# SPI_To_Ethernet.net
KiCad netlist of a schematic drawn in Altium Designer
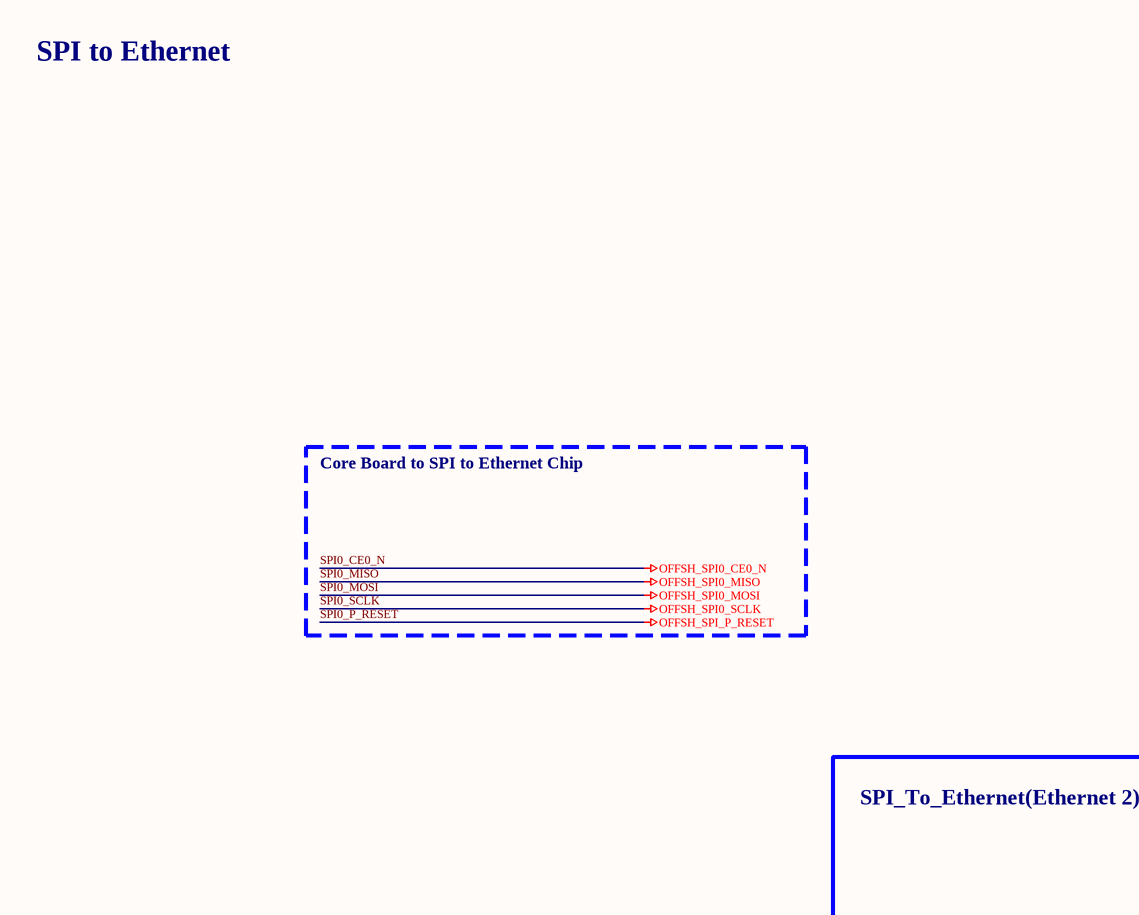
[diagram p0: SPI_To_Ethernet.SchDoc, top left]
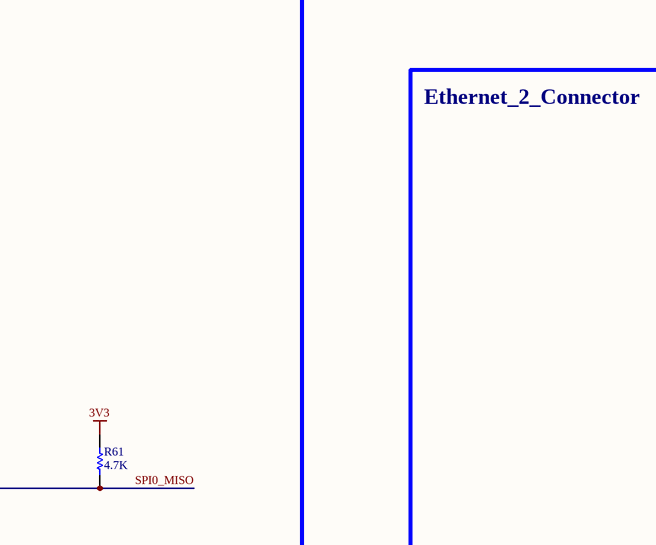
[diagram p1: SPI_To_Ethernet.SchDoc, top right]
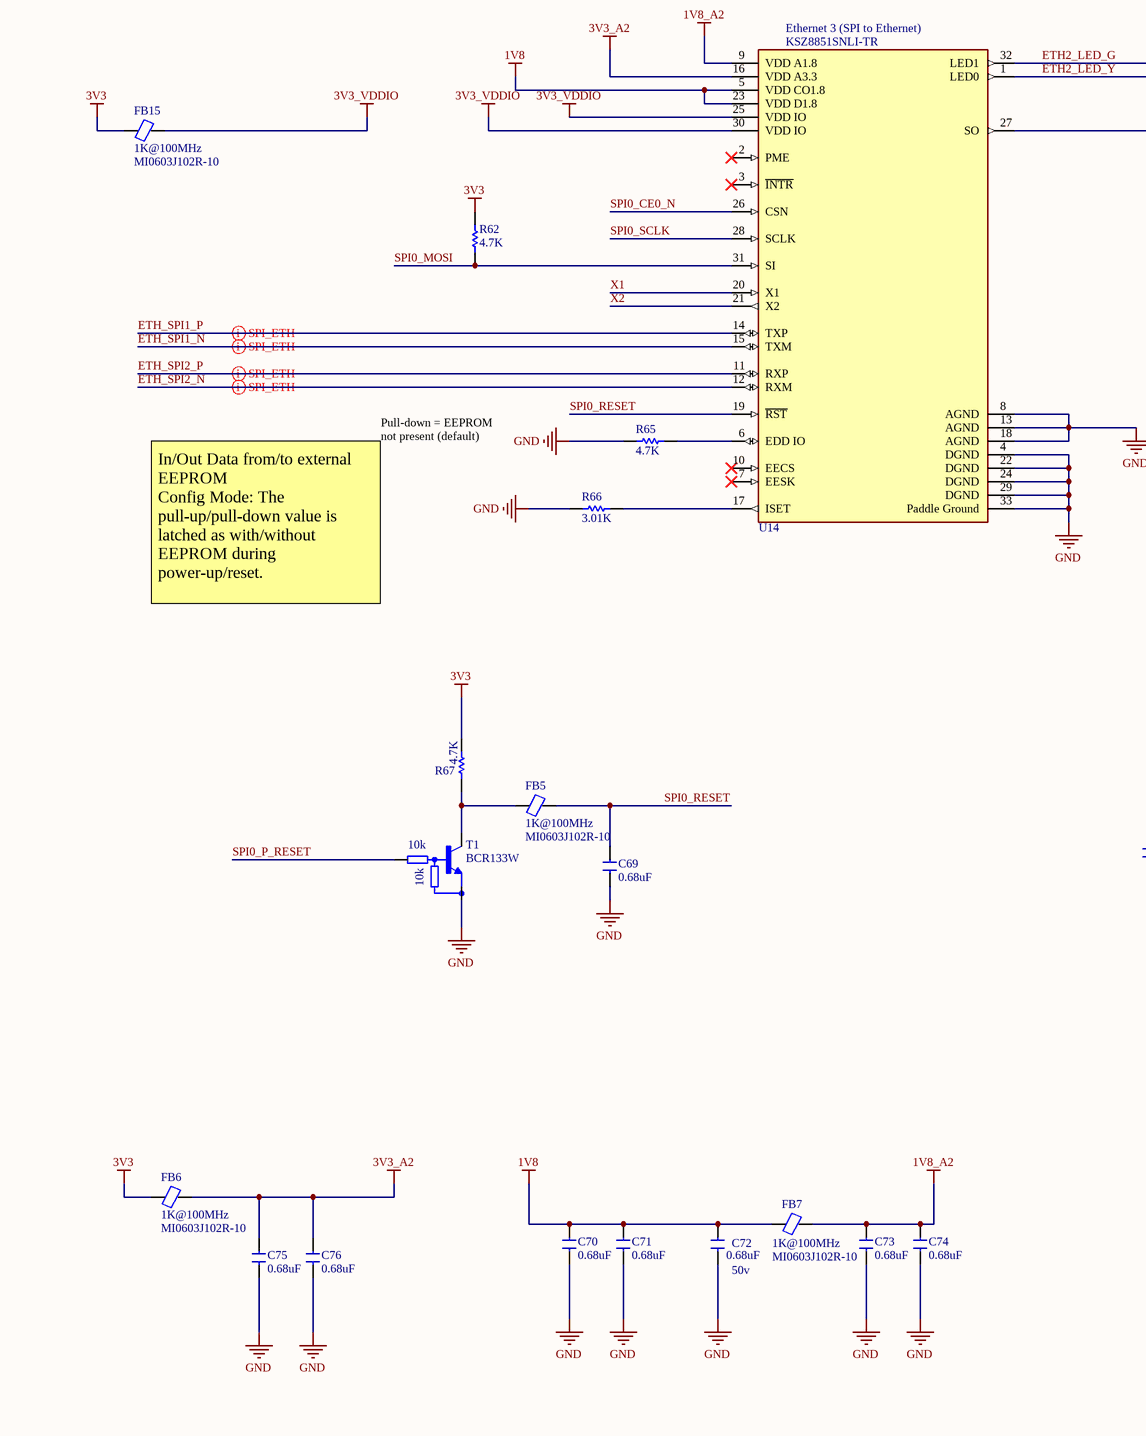
[diagram p2: SPI_To_Ethernet.SchDoc, bottom left]
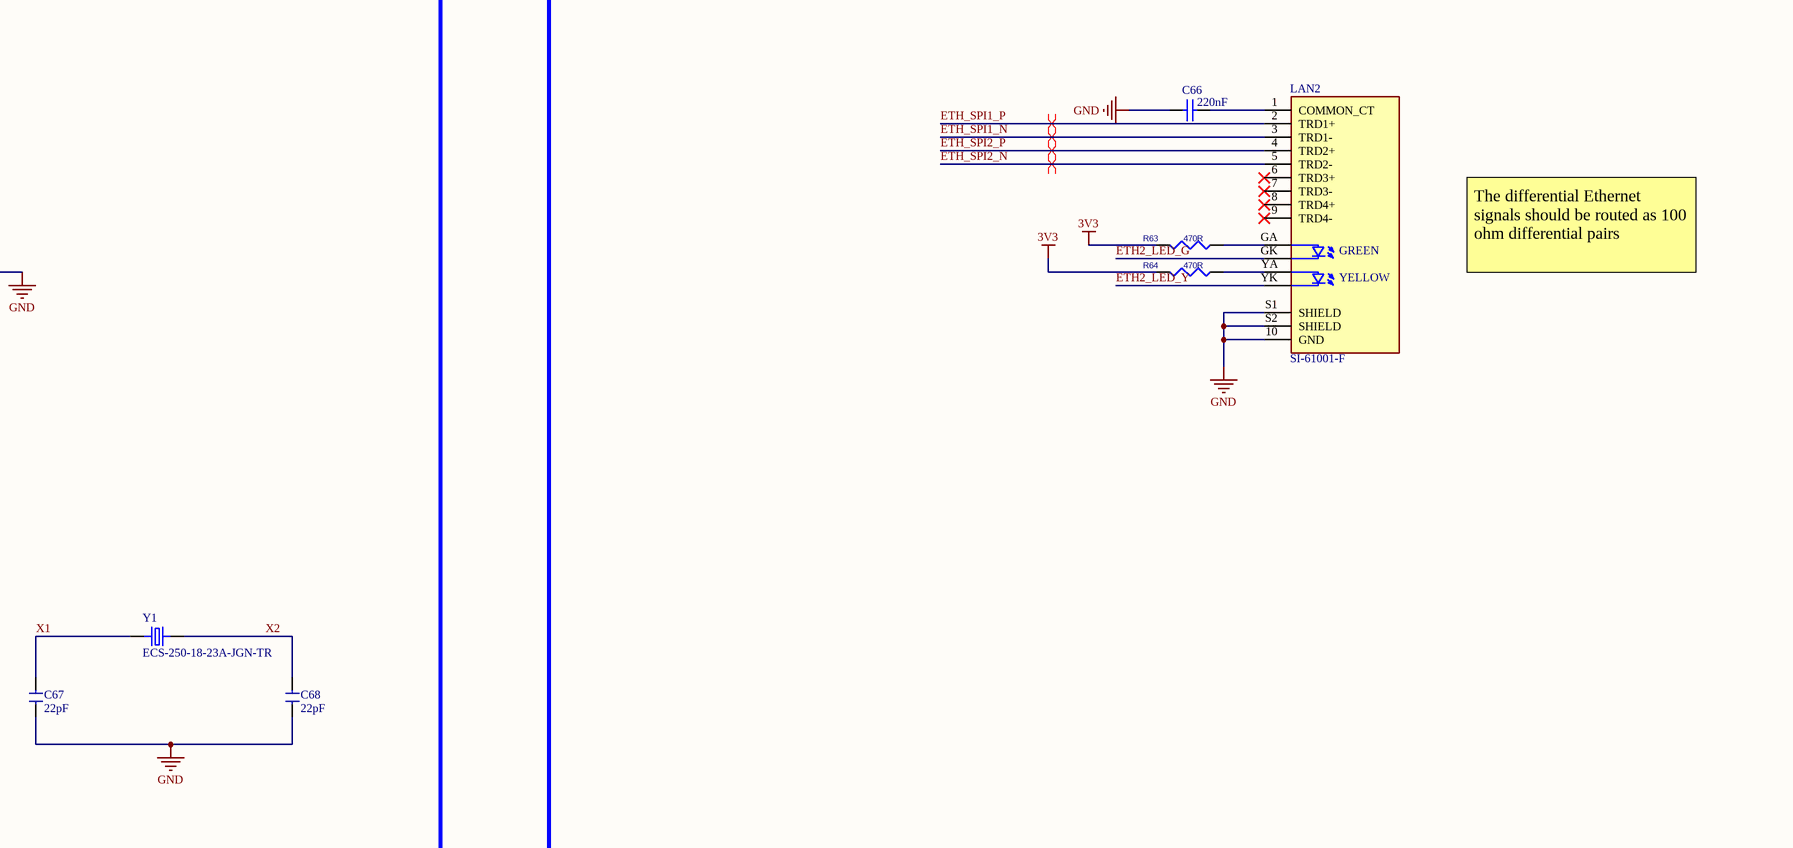
[diagram p3: SPI_To_Ethernet.SchDoc, bottom right]

(export (version "E")
  (design (tool "Eeschema 10.0.6"))
  (components
    (comp (ref "C66")
      (value "220nF")
      (footprint "CAP (0603)")
      (description "SMD capacitor")
      (fields (field (name "PART NUMBER") "SMD CAP (0603)") (field (name "Comment") "Cap"))
      (libsource (lib "CC") (part "Cap"))
    )
    (comp (ref "C67")
      (value "22pF")
      (footprint "0603 Capacitor")
      (fields (field (name "VOLTAGE") "50v") (field (name "Comment") "Capacitor SMD"))
      (libsource (lib "SA-C7_Apr09") (part "Capacitor SMD"))
    )
    (comp (ref "C68")
      (value "22pF")
      (footprint "0603 Capacitor")
      (fields (field (name "VOLTAGE") "50v") (field (name "Comment") "Capacitor SMD"))
      (libsource (lib "SA-C7_Apr09") (part "Capacitor SMD"))
    )
    (comp (ref "C69")
      (value "0.68uF")
      (footprint "0603 Capacitor")
      (fields (field (name "VOLTAGE") "50v") (field (name "Comment") "Capacitor SMD"))
      (libsource (lib "SA-C7_Apr09") (part "Capacitor SMD"))
    )
    (comp (ref "C70")
      (value "0.68uF")
      (footprint "0603 Capacitor")
      (fields (field (name "VOLTAGE") "50v") (field (name "Comment") "Capacitor SMD"))
      (libsource (lib "SA-C7_Apr09") (part "Capacitor SMD"))
    )
    (comp (ref "C71")
      (value "0.68uF")
      (footprint "0603 Capacitor")
      (fields (field (name "VOLTAGE") "50v") (field (name "Comment") "Capacitor SMD"))
      (libsource (lib "SA-C7_Apr09") (part "Capacitor SMD"))
    )
    (comp (ref "C72")
      (value "0.68uF")
      (footprint "0603 Capacitor")
      (fields (field (name "VOLTAGE") "50v") (field (name "Comment") "Capacitor SMD"))
      (libsource (lib "SA-C7_Apr09") (part "Capacitor SMD"))
    )
    (comp (ref "C73")
      (value "0.68uF")
      (footprint "0603 Capacitor")
      (fields (field (name "VOLTAGE") "50v") (field (name "Comment") "Capacitor SMD"))
      (libsource (lib "SA-C7_Apr09") (part "Capacitor SMD"))
    )
    (comp (ref "C74")
      (value "0.68uF")
      (footprint "0603 Capacitor")
      (fields (field (name "VOLTAGE") "50v") (field (name "Comment") "Capacitor SMD"))
      (libsource (lib "SA-C7_Apr09") (part "Capacitor SMD"))
    )
    (comp (ref "C75")
      (value "0.68uF")
      (footprint "0603 Capacitor")
      (fields (field (name "VOLTAGE") "50v") (field (name "Comment") "Capacitor SMD"))
      (libsource (lib "SA-C7_Apr09") (part "Capacitor SMD"))
    )
    (comp (ref "C76")
      (value "0.68uF")
      (footprint "0603 Capacitor")
      (fields (field (name "VOLTAGE") "50v") (field (name "Comment") "Capacitor SMD"))
      (libsource (lib "SA-C7_Apr09") (part "Capacitor SMD"))
    )
    (comp (ref "FB5")
      (value "1K@100MHz")
      (footprint "FB0603")
      (description "Ferrite Bead SMD")
      (fields (field (name "PART NUMBER") "MI0603J102R-10") (field (name "Comment") "Ferrite Bead"))
      (libsource (lib "*") (part "Ferrite Bead"))
    )
    (comp (ref "FB6")
      (value "1K@100MHz")
      (footprint "FB0603")
      (description "Ferrite Bead SMD")
      (fields (field (name "PART NUMBER") "MI0603J102R-10") (field (name "Comment") "Ferrite Bead"))
      (libsource (lib "*") (part "Ferrite Bead"))
    )
    (comp (ref "FB7")
      (value "1K@100MHz")
      (footprint "FB0603")
      (description "Ferrite Bead SMD")
      (fields (field (name "PART NUMBER") "MI0603J102R-10") (field (name "Comment") "Ferrite Bead"))
      (libsource (lib "*") (part "Ferrite Bead"))
    )
    (comp (ref "FB15")
      (value "1K@100MHz")
      (footprint "FB0603")
      (description "Ferrite Bead SMD")
      (fields (field (name "PART NUMBER") "MI0603J102R-10") (field (name "Comment") "Ferrite Bead"))
      (libsource (lib "*") (part "Ferrite Bead"))
    )
    (comp (ref "LAN2")
      (value "SI-61001-F")
      (footprint "SI-61001-F_with3D:BEL_SI-61001-F")
      (description "Conn RJ-45 RCP 8 POS 1.27mm Solder RA Thru-Hole 14 Terminal 1 Port")
      (fields (field (name "MF") "Bel Magnetic Solutions"))
      (libsource (lib "SI-61001-F (1)") (part "SI-61001-F"))
    )
    (comp (ref "R61")
      (value "4.7K")
      (footprint "R0603")
      (description "Resistor")
      (fields (field (name "Comment") "Res") (field (name "PUBLISHER") "Altium Limited"))
      (libsource (lib "SCV500+") (part "Res"))
    )
    (comp (ref "R62")
      (value "4.7K")
      (footprint "R0603")
      (description "Resistor")
      (fields (field (name "Comment") "Res") (field (name "PUBLISHER") "Altium Limited"))
      (libsource (lib "SCV500+") (part "Res"))
    )
    (comp (ref "R63") (value "470R") (footprint "R0603") (libsource (lib "*") (part "RES")))
    (comp (ref "R64") (value "470R") (footprint "R0603") (libsource (lib "*") (part "RES")))
    (comp (ref "R65")
      (value "4.7K")
      (footprint "R0603")
      (description "Resistor")
      (fields (field (name "Comment") "Res") (field (name "PUBLISHER") "Altium Limited"))
      (libsource (lib "SCV500+") (part "Res"))
    )
    (comp (ref "R66")
      (value "3.01K")
      (footprint "R0603")
      (description "Resistor")
      (fields (field (name "Comment") "Res") (field (name "PUBLISHER") "Altium Limited"))
      (libsource (lib "SCV500+") (part "Res"))
    )
    (comp (ref "R67")
      (value "4.7K")
      (footprint "R0603")
      (description "Resistor")
      (fields (field (name "Comment") "Res") (field (name "PUBLISHER") "Altium Limited"))
      (libsource (lib "SCV500+") (part "Res"))
    )
    (comp (ref "T1")
      (value "BCR133W")
      (footprint "SOT323-BEC")
      (description "<b>NPN Silicon Digital Transistor</b>  50V 0,1A 0,25W")
      (libsource (lib "BCR133W") (part "BCR133W"))
    )
    (comp (ref "U14")
      (value "KSZ8851SNLI-TR")
      (footprint "QFN50P500X500X90-33N")
      (libsource (lib "IC_Microchip_KSZ8851SNLI-TR_eec") (part "KSZ8851SNLI-TR"))
    )
    (comp (ref "Y1")
      (value "ECS-250-18-23A-JGN-TR")
      (footprint "XTAL_ECS-250-18-23A-JGN-TR")
      (description "Crystal 2-SMD, No Lead")
      (libsource (lib "ECS-250-18-23A-JGN-TR") (part "ECS-250-18-23A-JGN-TR"))
    )
  )
  (nets
    (net (code "1") (name "/ETH2_LED_G") (class "Default")
      (node (ref "LAN2") (pin "GK") (pinfunction "GK_GK") (pintype "passive"))
      (node (ref "U14") (pin "32") (pinfunction "LED1_32") (pintype "output"))
    )
    (net (code "2") (name "/ETH2_LED_Y") (class "Default")
      (node (ref "LAN2") (pin "YK") (pinfunction "YK_YK") (pintype "passive"))
      (node (ref "U14") (pin "1") (pinfunction "LED0_1") (pintype "output"))
    )
    (net (code "3") (name "/ETH_SPI1_N") (class "Default")
      (node (ref "LAN2") (pin "3") (pinfunction "TRD1-_3") (pintype "passive"))
      (node (ref "U14") (pin "15") (pinfunction "TXM_15") (pintype "bidirectional"))
    )
    (net (code "4") (name "/ETH_SPI1_P") (class "Default")
      (node (ref "LAN2") (pin "2") (pinfunction "TRD1+_2") (pintype "passive"))
      (node (ref "U14") (pin "14") (pinfunction "TXP_14") (pintype "bidirectional"))
    )
    (net (code "5") (name "/ETH_SPI2_N") (class "Default")
      (node (ref "LAN2") (pin "5") (pinfunction "TRD2-_5") (pintype "passive"))
      (node (ref "U14") (pin "12") (pinfunction "RXM_12") (pintype "bidirectional"))
    )
    (net (code "6") (name "/ETH_SPI2_P") (class "Default")
      (node (ref "LAN2") (pin "4") (pinfunction "TRD2+_4") (pintype "passive"))
      (node (ref "U14") (pin "11") (pinfunction "RXP_11") (pintype "bidirectional"))
    )
    (net (code "7") (name "/SPI0_RESET") (class "Default")
      (node (ref "C69") (pin "1") (pintype "passive"))
      (node (ref "FB5") (pin "2") (pinfunction "2_2") (pintype "passive"))
      (node (ref "U14") (pin "19") (pinfunction "~{RST}_19") (pintype "input"))
    )
    (net (code "8") (name "/X1") (class "Default")
      (node (ref "C67") (pin "1") (pintype "passive"))
      (node (ref "U14") (pin "20") (pinfunction "X1_20") (pintype "input"))
      (node (ref "Y1") (pin "1") (pinfunction "IN/OUT_1") (pintype "passive"))
    )
    (net (code "9") (name "/X2") (class "Default")
      (node (ref "C68") (pin "1") (pintype "passive"))
      (node (ref "U14") (pin "21") (pinfunction "X2_21") (pintype "output"))
      (node (ref "Y1") (pin "2") (pinfunction "OUT/IN_2") (pintype "passive"))
    )
    (net (code "10") (name "1V8") (class "Default")
      (node (ref "C70") (pin "1") (pintype "passive"))
      (node (ref "C71") (pin "1") (pintype "passive"))
      (node (ref "C72") (pin "2") (pintype "passive"))
      (node (ref "FB7") (pin "1") (pinfunction "1_1") (pintype "passive"))
      (node (ref "U14") (pin "23") (pinfunction "VDD_D1.8_23") (pintype "power_in"))
      (node (ref "U14") (pin "5") (pinfunction "VDD_CO1.8_5") (pintype "power_in"))
    )
    (net (code "11") (name "1V8_A2") (class "Default")
      (node (ref "C73") (pin "1") (pintype "passive"))
      (node (ref "C74") (pin "1") (pintype "passive"))
      (node (ref "FB7") (pin "2") (pinfunction "2_2") (pintype "passive"))
      (node (ref "U14") (pin "9") (pinfunction "VDD_A1.8_9") (pintype "power_in"))
    )
    (net (code "12") (name "3V3") (class "Default")
      (node (ref "FB15") (pin "1") (pinfunction "1_1") (pintype "passive"))
      (node (ref "FB6") (pin "1") (pinfunction "1_1") (pintype "passive"))
      (node (ref "R61") (pin "2") (pinfunction "2_2") (pintype "passive"))
      (node (ref "R62") (pin "2") (pinfunction "2_2") (pintype "passive"))
      (node (ref "R63") (pin "1") (pinfunction "1_1") (pintype "passive"))
      (node (ref "R64") (pin "1") (pinfunction "1_1") (pintype "passive"))
      (node (ref "R67") (pin "2") (pinfunction "2_2") (pintype "passive"))
    )
    (net (code "13") (name "3V3_A2") (class "Default")
      (node (ref "C75") (pin "1") (pintype "passive"))
      (node (ref "C76") (pin "1") (pintype "passive"))
      (node (ref "FB6") (pin "2") (pinfunction "2_2") (pintype "passive"))
      (node (ref "U14") (pin "16") (pinfunction "VDD_A3.3_16") (pintype "power_in"))
    )
    (net (code "14") (name "3V3_VDDIO") (class "Default")
      (node (ref "FB15") (pin "2") (pinfunction "2_2") (pintype "passive"))
      (node (ref "U14") (pin "25") (pinfunction "VDD_IO_25") (pintype "power_in"))
      (node (ref "U14") (pin "30") (pinfunction "VDD_IO_30") (pintype "power_in"))
    )
    (net (code "15") (name "GND") (class "Default")
      (node (ref "C66") (pin "1") (pinfunction "1_1") (pintype "passive"))
      (node (ref "C67") (pin "2") (pintype "passive"))
      (node (ref "C68") (pin "2") (pintype "passive"))
      (node (ref "C69") (pin "2") (pintype "passive"))
      (node (ref "C70") (pin "2") (pintype "passive"))
      (node (ref "C71") (pin "2") (pintype "passive"))
      (node (ref "C72") (pin "1") (pintype "passive"))
      (node (ref "C73") (pin "2") (pintype "passive"))
      (node (ref "C74") (pin "2") (pintype "passive"))
      (node (ref "C75") (pin "2") (pintype "passive"))
      (node (ref "C76") (pin "2") (pintype "passive"))
      (node (ref "LAN2") (pin "10") (pinfunction "GND_10") (pintype "power_in"))
      (node (ref "LAN2") (pin "S1") (pinfunction "SHIELD_S1") (pintype "passive"))
      (node (ref "LAN2") (pin "S2") (pinfunction "SHIELD_S2") (pintype "passive"))
      (node (ref "R65") (pin "1") (pinfunction "1_1") (pintype "passive"))
      (node (ref "R66") (pin "1") (pinfunction "1_1") (pintype "passive"))
      (node (ref "T1") (pin "E") (pinfunction "E_E") (pintype "passive"))
      (node (ref "U14") (pin "13") (pinfunction "AGND_13") (pintype "power_in"))
      (node (ref "U14") (pin "18") (pinfunction "AGND_18") (pintype "power_in"))
      (node (ref "U14") (pin "22") (pinfunction "DGND_22") (pintype "power_in"))
      (node (ref "U14") (pin "24") (pinfunction "DGND_24") (pintype "power_in"))
      (node (ref "U14") (pin "29") (pinfunction "DGND_29") (pintype "power_in"))
      (node (ref "U14") (pin "33") (pinfunction "Paddle_Ground_33") (pintype "passive"))
      (node (ref "U14") (pin "4") (pinfunction "DGND_4") (pintype "power_in"))
      (node (ref "U14") (pin "8") (pinfunction "AGND_8") (pintype "power_in"))
    )
    (net (code "16") (name "Net-(FB5-Pad1)") (class "Default")
      (node (ref "FB5") (pin "1") (pinfunction "1_1") (pintype "passive"))
      (node (ref "R67") (pin "1") (pinfunction "1_1") (pintype "passive"))
      (node (ref "T1") (pin "C") (pinfunction "C_C") (pintype "passive"))
    )
    (net (code "17") (name "Net-(LAN2-COMMON_CT)") (class "Default")
      (node (ref "C66") (pin "2") (pinfunction "2_2") (pintype "passive"))
      (node (ref "LAN2") (pin "1") (pinfunction "COMMON_CT_1") (pintype "passive"))
    )
    (net (code "18") (name "Net-(LAN2-PadGA)") (class "Default")
      (node (ref "LAN2") (pin "GA") (pinfunction "GA_GA") (pintype "passive"))
      (node (ref "R63") (pin "2") (pinfunction "2_2") (pintype "passive"))
    )
    (net (code "19") (name "Net-(LAN2-PadYA)") (class "Default")
      (node (ref "LAN2") (pin "YA") (pinfunction "YA_YA") (pintype "passive"))
      (node (ref "R64") (pin "2") (pinfunction "2_2") (pintype "passive"))
    )
    (net (code "20") (name "Net-(U14-EDD_IO)") (class "Default")
      (node (ref "R65") (pin "2") (pinfunction "2_2") (pintype "passive"))
      (node (ref "U14") (pin "6") (pinfunction "EDD_IO_6") (pintype "bidirectional"))
    )
    (net (code "21") (name "Net-(U14-ISET)") (class "Default")
      (node (ref "R66") (pin "2") (pinfunction "2_2") (pintype "passive"))
      (node (ref "U14") (pin "17") (pinfunction "ISET_17") (pintype "output"))
    )
    (net (code "22") (name "OFFSH_SPI0_CE0_N") (class "Default")
      (node (ref "U14") (pin "26") (pinfunction "CSN_26") (pintype "input"))
    )
    (net (code "23") (name "OFFSH_SPI0_MISO") (class "Default")
      (node (ref "R61") (pin "1") (pinfunction "1_1") (pintype "passive"))
      (node (ref "U14") (pin "27") (pinfunction "SO_27") (pintype "output"))
    )
    (net (code "24") (name "OFFSH_SPI0_MOSI") (class "Default")
      (node (ref "R62") (pin "1") (pinfunction "1_1") (pintype "passive"))
      (node (ref "U14") (pin "31") (pinfunction "SI_31") (pintype "input"))
    )
    (net (code "25") (name "OFFSH_SPI0_SCLK") (class "Default")
      (node (ref "U14") (pin "28") (pinfunction "SCLK_28") (pintype "input"))
    )
    (net (code "26") (name "OFFSH_SPI_P_RESET") (class "Default")
      (node (ref "T1") (pin "B") (pinfunction "B_B") (pintype "passive"))
    )
    (net (code "27") (name "unconnected-(LAN2-TRD3+-Pad6)") (class "Default")
      (node (ref "LAN2") (pin "6") (pinfunction "TRD3+_6") (pintype "passive+no_connect"))
    )
    (net (code "28") (name "unconnected-(LAN2-TRD3--Pad7)") (class "Default")
      (node (ref "LAN2") (pin "7") (pinfunction "TRD3-_7") (pintype "passive+no_connect"))
    )
    (net (code "29") (name "unconnected-(LAN2-TRD4+-Pad8)") (class "Default")
      (node (ref "LAN2") (pin "8") (pinfunction "TRD4+_8") (pintype "passive+no_connect"))
    )
    (net (code "30") (name "unconnected-(LAN2-TRD4--Pad9)") (class "Default")
      (node (ref "LAN2") (pin "9") (pinfunction "TRD4-_9") (pintype "passive+no_connect"))
    )
    (net (code "31") (name "unconnected-(U14-EECS-Pad10)") (class "Default")
      (node (ref "U14") (pin "10") (pinfunction "EECS_10") (pintype "input+no_connect"))
    )
    (net (code "32") (name "unconnected-(U14-EESK-Pad7)") (class "Default")
      (node (ref "U14") (pin "7") (pinfunction "EESK_7") (pintype "input+no_connect"))
    )
    (net (code "33") (name "unconnected-(U14-PME-Pad2)") (class "Default")
      (node (ref "U14") (pin "2") (pinfunction "PME_2") (pintype "input+no_connect"))
    )
    (net (code "34") (name "unconnected-(U14-~{INTR}-Pad3)") (class "Default")
      (node (ref "U14") (pin "3") (pinfunction "~{INTR}_3") (pintype "input+no_connect"))
    )
  )
)
